# SCH_Designing_a_PCB_1__2022-05-29.net
KiCad netlist of a schematic drawn in EasyEDA
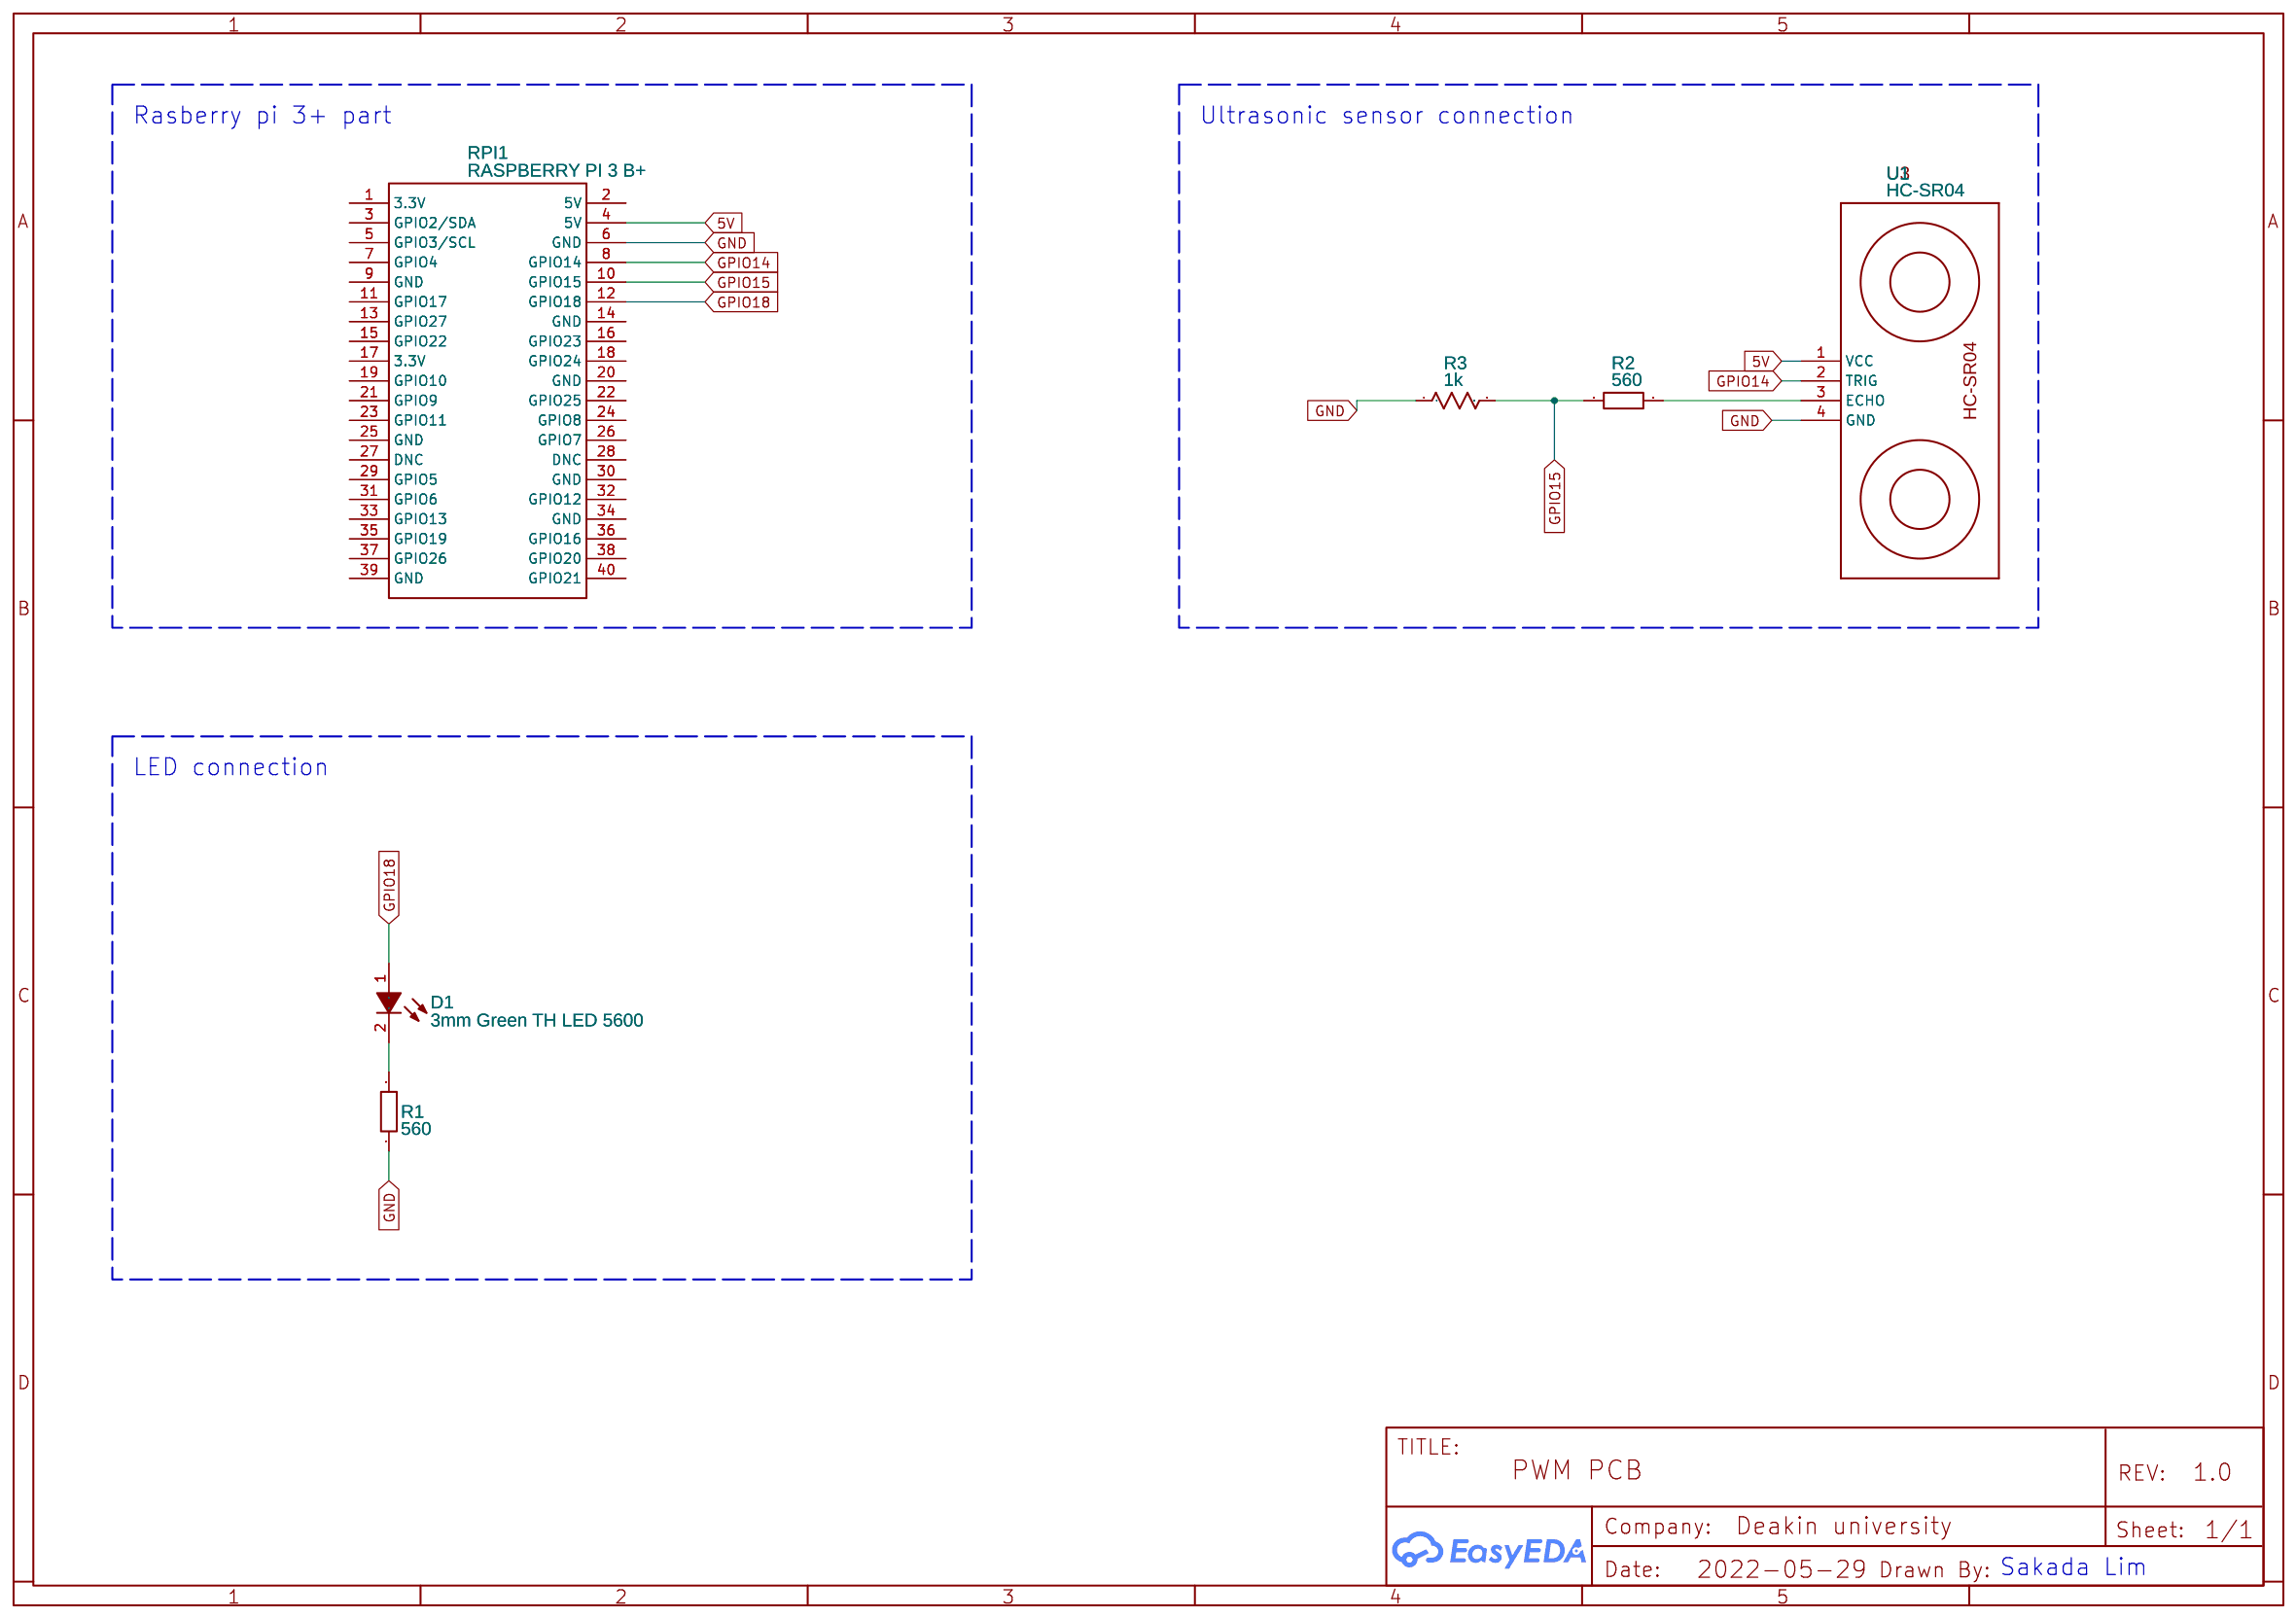
[diagram p0: schematic sheet]

(export (version "E")
  (design (tool "Eeschema 10.0.6"))
  (components
    (comp (ref "D1")
      (value "3mm Green TH LED 5600")
      (fields (field (name "BOM_Manufacturer Part") "5600") (field (name "BOM_Supplier Part") "L20325-ND"))
      (libsource (lib "") (part "3mm Green TH LED 5600"))
    )
    (comp (ref "R1") (value "560") (libsource (lib "") (part "560_1")))
    (comp (ref "R2") (value "560") (libsource (lib "") (part "560")))
    (comp (ref "R3")
      (value "1k")
      (fields
        (field (name "BOM_Manufacturer Part") "MCF 0.25W 10K")
        (field (name "BOM_Supplier Part") "9339051")
      )
      (libsource (lib "") (part "1k"))
    )
    (comp (ref "RPI1")
      (value "RASPBERRY PI 3 B+")
      (fields
        (field (name "Manufacturer") "Raspberry Pi")
        (field (name "BOM_Manufacturer Part") "Raspberry Pi 3 - Model B+ - 1.4GHz Cortex-A53 with 1GB RAM")
        (field (name "BOM_Supplier Part") "3775")
      )
      (libsource (lib "") (part "RASPBERRY PI 3 B+"))
    )
    (comp (ref "U1")
      (value "HC-SR04")
      (fields (field (name "BOM_Manufacturer Part") "ServoMotor"))
      (libsource (lib "") (part "HC-SR04"))
    )
  )
  (nets
    (net (code "1") (name "5V") (class "Default")
      (node (ref "RPI1") (pin "4") (pinfunction "5V_4") (pintype "passive"))
      (node (ref "U1") (pin "1") (pinfunction "VCC_1") (pintype "passive"))
    )
    (net (code "2") (name "GND") (class "Default")
      (node (ref "R1") (pin "1") (pintype "unspecified"))
      (node (ref "R3") (pin "1") (pinfunction "1_1") (pintype "unspecified"))
      (node (ref "RPI1") (pin "6") (pinfunction "GND_6") (pintype "unspecified"))
      (node (ref "U1") (pin "4") (pinfunction "GND_4") (pintype "passive"))
    )
    (net (code "3") (name "GPIO14") (class "Default")
      (node (ref "RPI1") (pin "8") (pinfunction "GPIO14_8") (pintype "bidirectional"))
      (node (ref "U1") (pin "2") (pinfunction "TRIG_2") (pintype "input"))
    )
    (net (code "4") (name "GPIO15") (class "Default")
      (node (ref "R2") (pin "1") (pintype "unspecified"))
      (node (ref "R3") (pin "2") (pinfunction "2_2") (pintype "unspecified"))
      (node (ref "RPI1") (pin "10") (pinfunction "GPIO15_10") (pintype "bidirectional"))
    )
    (net (code "5") (name "GPIO18") (class "Default")
      (node (ref "D1") (pin "1") (pinfunction "A_1") (pintype "input"))
      (node (ref "RPI1") (pin "12") (pinfunction "GPIO18_12") (pintype "bidirectional"))
    )
    (net (code "6") (name "Net-(D1-K)") (class "Default")
      (node (ref "D1") (pin "2") (pinfunction "K_2") (pintype "input"))
      (node (ref "R1") (pin "2") (pintype "unspecified"))
    )
    (net (code "7") (name "Net-(U1-ECHO)") (class "Default")
      (node (ref "R2") (pin "2") (pintype "unspecified"))
      (node (ref "U1") (pin "3") (pinfunction "ECHO_3") (pintype "output"))
    )
    (net (code "8") (name "unconnected-(RPI1-3.3V-Pad1)") (class "Default")
      (node (ref "RPI1") (pin "1") (pinfunction "3.3V_1") (pintype "passive"))
    )
    (net (code "9") (name "unconnected-(RPI1-3.3V-Pad17)") (class "Default")
      (node (ref "RPI1") (pin "17") (pinfunction "3.3V_17") (pintype "passive"))
    )
    (net (code "10") (name "unconnected-(RPI1-5V-Pad2)") (class "Default")
      (node (ref "RPI1") (pin "2") (pinfunction "5V_2") (pintype "passive"))
    )
    (net (code "11") (name "unconnected-(RPI1-DNC-Pad27)") (class "Default")
      (node (ref "RPI1") (pin "27") (pinfunction "DNC_27") (pintype "unspecified"))
    )
    (net (code "12") (name "unconnected-(RPI1-DNC-Pad28)") (class "Default")
      (node (ref "RPI1") (pin "28") (pinfunction "DNC_28") (pintype "unspecified"))
    )
    (net (code "13") (name "unconnected-(RPI1-GND-Pad9)") (class "Default")
      (node (ref "RPI1") (pin "9") (pinfunction "GND_9") (pintype "unspecified"))
    )
    (net (code "14") (name "unconnected-(RPI1-GND-Pad14)") (class "Default")
      (node (ref "RPI1") (pin "14") (pinfunction "GND_14") (pintype "unspecified"))
    )
    (net (code "15") (name "unconnected-(RPI1-GND-Pad20)") (class "Default")
      (node (ref "RPI1") (pin "20") (pinfunction "GND_20") (pintype "unspecified"))
    )
    (net (code "16") (name "unconnected-(RPI1-GND-Pad25)") (class "Default")
      (node (ref "RPI1") (pin "25") (pinfunction "GND_25") (pintype "unspecified"))
    )
    (net (code "17") (name "unconnected-(RPI1-GND-Pad30)") (class "Default")
      (node (ref "RPI1") (pin "30") (pinfunction "GND_30") (pintype "unspecified"))
    )
    (net (code "18") (name "unconnected-(RPI1-GND-Pad34)") (class "Default")
      (node (ref "RPI1") (pin "34") (pinfunction "GND_34") (pintype "unspecified"))
    )
    (net (code "19") (name "unconnected-(RPI1-GND-Pad39)") (class "Default")
      (node (ref "RPI1") (pin "39") (pinfunction "GND_39") (pintype "unspecified"))
    )
    (net (code "20") (name "unconnected-(RPI1-GPIO2{slash}SDA-Pad3)") (class "Default")
      (node (ref "RPI1") (pin "3") (pinfunction "GPIO2/SDA_3") (pintype "bidirectional"))
    )
    (net (code "21") (name "unconnected-(RPI1-GPIO3{slash}SCL-Pad5)") (class "Default")
      (node (ref "RPI1") (pin "5") (pinfunction "GPIO3/SCL_5") (pintype "bidirectional"))
    )
    (net (code "22") (name "unconnected-(RPI1-GPIO4-Pad7)") (class "Default")
      (node (ref "RPI1") (pin "7") (pinfunction "GPIO4_7") (pintype "bidirectional"))
    )
    (net (code "23") (name "unconnected-(RPI1-GPIO5-Pad29)") (class "Default")
      (node (ref "RPI1") (pin "29") (pinfunction "GPIO5_29") (pintype "bidirectional"))
    )
    (net (code "24") (name "unconnected-(RPI1-GPIO6-Pad31)") (class "Default")
      (node (ref "RPI1") (pin "31") (pinfunction "GPIO6_31") (pintype "bidirectional"))
    )
    (net (code "25") (name "unconnected-(RPI1-GPIO7-Pad26)") (class "Default")
      (node (ref "RPI1") (pin "26") (pinfunction "GPIO7_26") (pintype "bidirectional"))
    )
    (net (code "26") (name "unconnected-(RPI1-GPIO8-Pad24)") (class "Default")
      (node (ref "RPI1") (pin "24") (pinfunction "GPIO8_24") (pintype "bidirectional"))
    )
    (net (code "27") (name "unconnected-(RPI1-GPIO9-Pad21)") (class "Default")
      (node (ref "RPI1") (pin "21") (pinfunction "GPIO9_21") (pintype "bidirectional"))
    )
    (net (code "28") (name "unconnected-(RPI1-GPIO10-Pad19)") (class "Default")
      (node (ref "RPI1") (pin "19") (pinfunction "GPIO10_19") (pintype "bidirectional"))
    )
    (net (code "29") (name "unconnected-(RPI1-GPIO11-Pad23)") (class "Default")
      (node (ref "RPI1") (pin "23") (pinfunction "GPIO11_23") (pintype "bidirectional"))
    )
    (net (code "30") (name "unconnected-(RPI1-GPIO12-Pad32)") (class "Default")
      (node (ref "RPI1") (pin "32") (pinfunction "GPIO12_32") (pintype "bidirectional"))
    )
    (net (code "31") (name "unconnected-(RPI1-GPIO13-Pad33)") (class "Default")
      (node (ref "RPI1") (pin "33") (pinfunction "GPIO13_33") (pintype "bidirectional"))
    )
    (net (code "32") (name "unconnected-(RPI1-GPIO16-Pad36)") (class "Default")
      (node (ref "RPI1") (pin "36") (pinfunction "GPIO16_36") (pintype "bidirectional"))
    )
    (net (code "33") (name "unconnected-(RPI1-GPIO17-Pad11)") (class "Default")
      (node (ref "RPI1") (pin "11") (pinfunction "GPIO17_11") (pintype "bidirectional"))
    )
    (net (code "34") (name "unconnected-(RPI1-GPIO19-Pad35)") (class "Default")
      (node (ref "RPI1") (pin "35") (pinfunction "GPIO19_35") (pintype "bidirectional"))
    )
    (net (code "35") (name "unconnected-(RPI1-GPIO20-Pad38)") (class "Default")
      (node (ref "RPI1") (pin "38") (pinfunction "GPIO20_38") (pintype "bidirectional"))
    )
    (net (code "36") (name "unconnected-(RPI1-GPIO21-Pad40)") (class "Default")
      (node (ref "RPI1") (pin "40") (pinfunction "GPIO21_40") (pintype "bidirectional"))
    )
    (net (code "37") (name "unconnected-(RPI1-GPIO22-Pad15)") (class "Default")
      (node (ref "RPI1") (pin "15") (pinfunction "GPIO22_15") (pintype "bidirectional"))
    )
    (net (code "38") (name "unconnected-(RPI1-GPIO23-Pad16)") (class "Default")
      (node (ref "RPI1") (pin "16") (pinfunction "GPIO23_16") (pintype "bidirectional"))
    )
    (net (code "39") (name "unconnected-(RPI1-GPIO24-Pad18)") (class "Default")
      (node (ref "RPI1") (pin "18") (pinfunction "GPIO24_18") (pintype "bidirectional"))
    )
    (net (code "40") (name "unconnected-(RPI1-GPIO25-Pad22)") (class "Default")
      (node (ref "RPI1") (pin "22") (pinfunction "GPIO25_22") (pintype "bidirectional"))
    )
    (net (code "41") (name "unconnected-(RPI1-GPIO26-Pad37)") (class "Default")
      (node (ref "RPI1") (pin "37") (pinfunction "GPIO26_37") (pintype "bidirectional"))
    )
    (net (code "42") (name "unconnected-(RPI1-GPIO27-Pad13)") (class "Default")
      (node (ref "RPI1") (pin "13") (pinfunction "GPIO27_13") (pintype "bidirectional"))
    )
  )
)
